# PIC18F97J94.net
KiCad netlist of a schematic drawn in Altium Designer
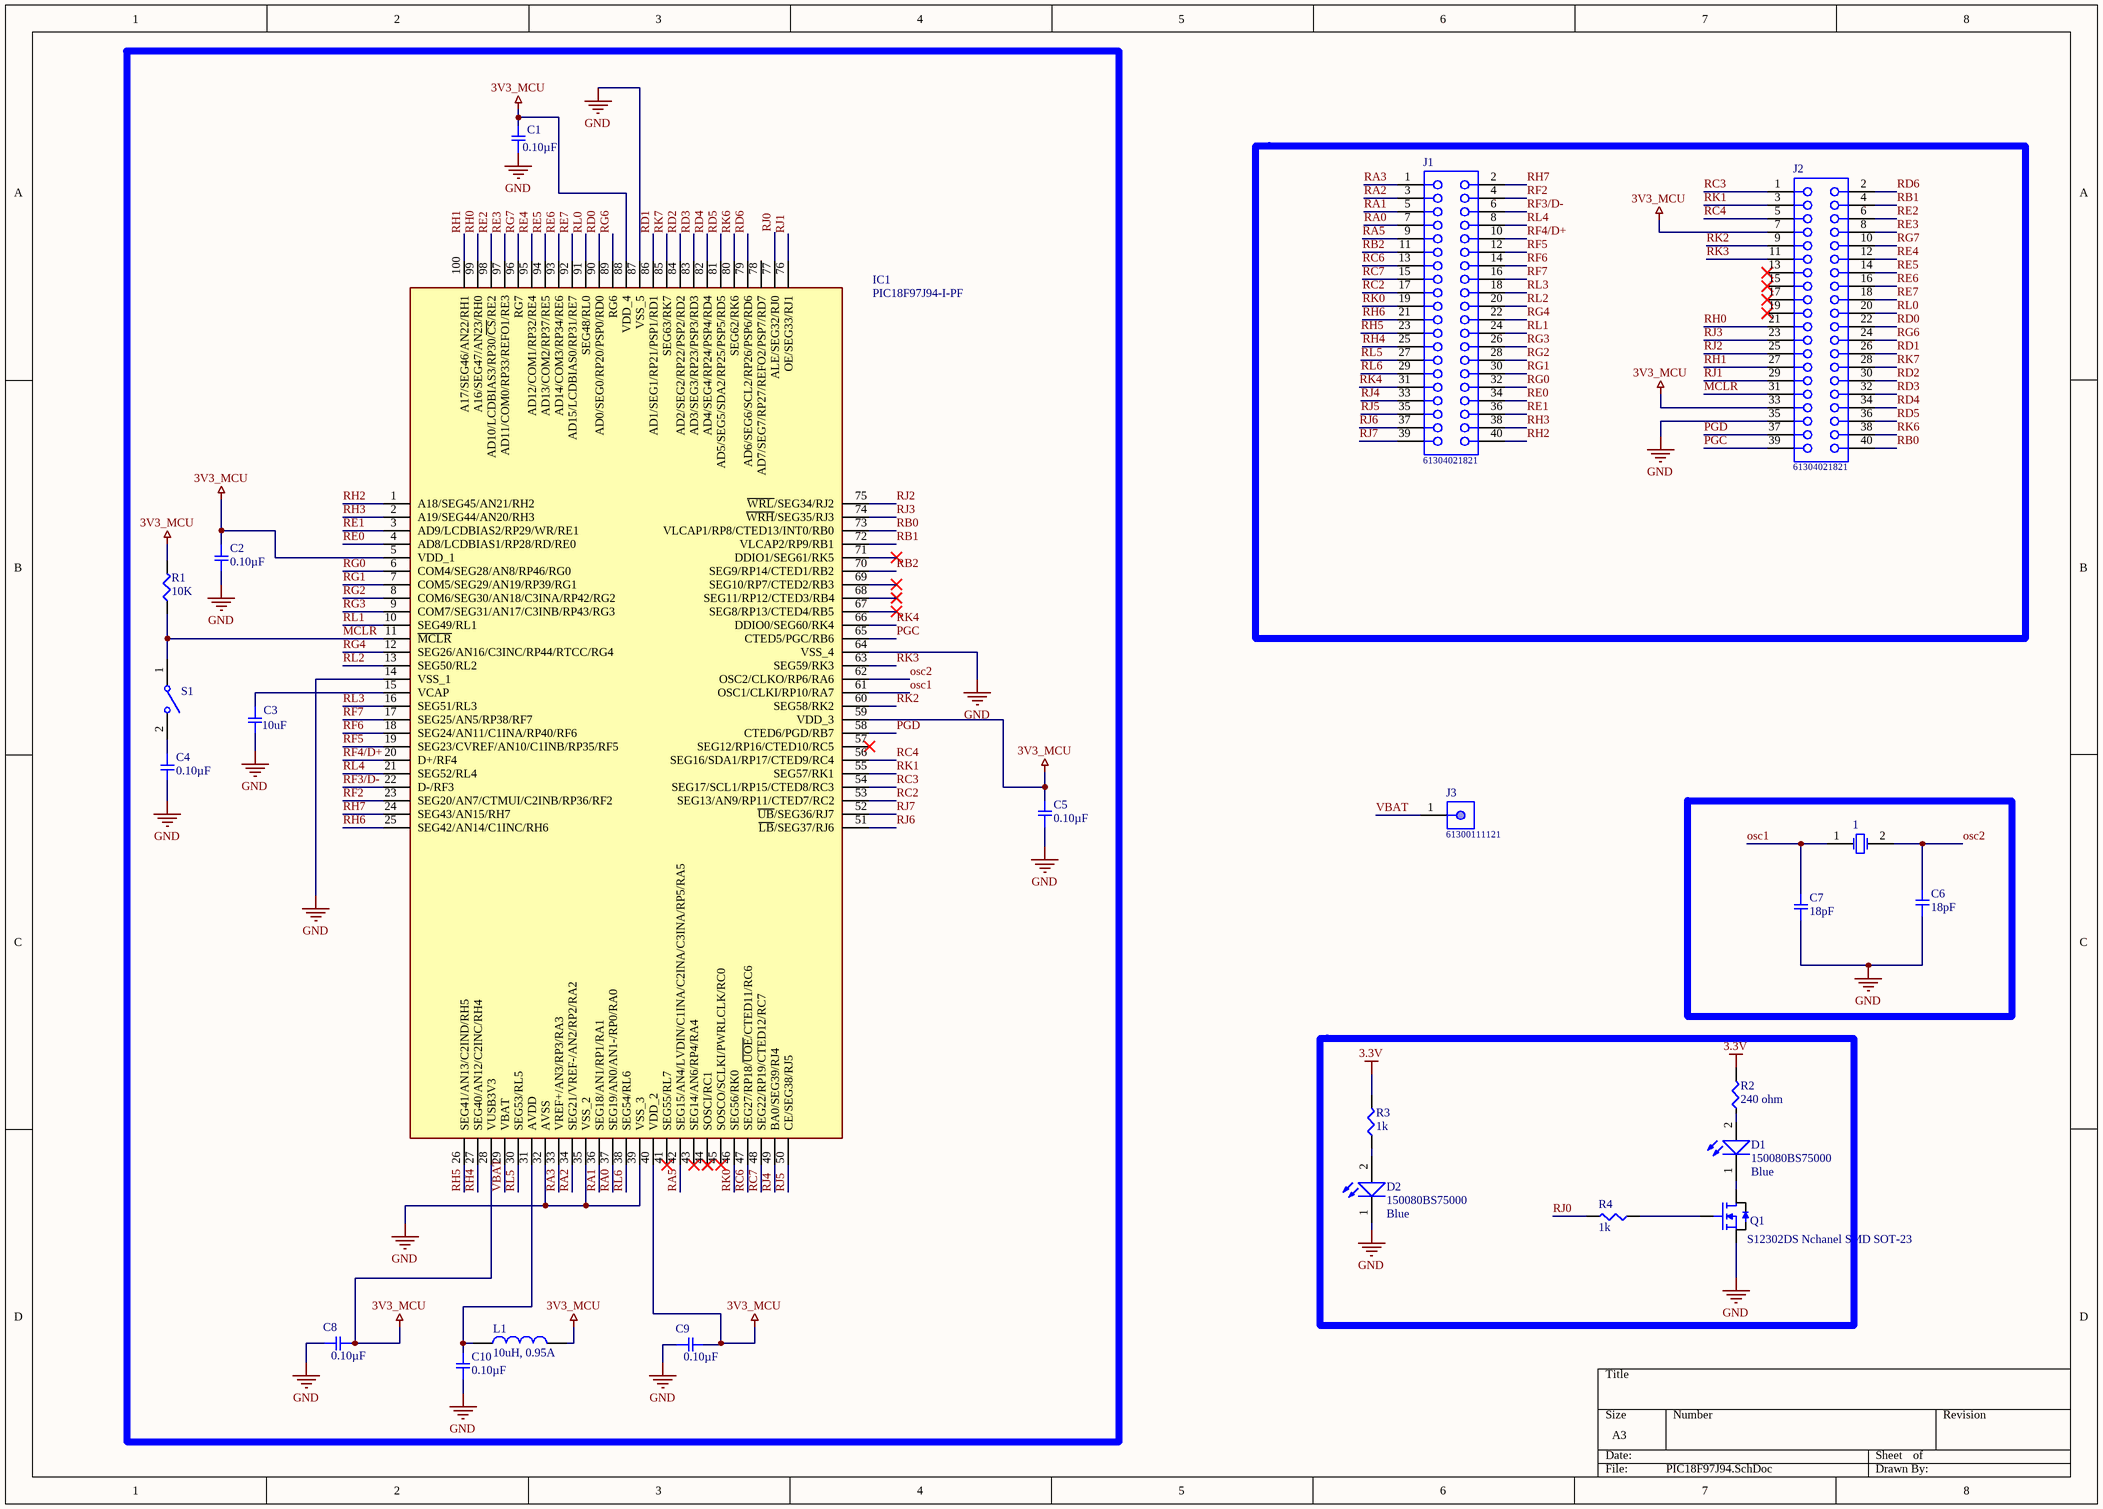
[diagram p0: PIC18F97J94.SchDoc]

(export (version "E")
  (design (tool "Eeschema 10.0.6"))
  (components
    (comp (ref "1")
      (value "~")
      (footprint "Mini Crystal")
      (description "9B-64.000MBBK-B")
      (fields (field (name "MANUFACTURER") "Abracon") (field (name "PARTNUMBER") "ABLS2-4.096MHZ-D4Y-T"))
      (libsource (lib "Medi Custom library") (part "Mini Crystal"))
    )
    (comp (ref "C1")
      (value "0.10µF")
      (footprint "SMD-0805C")
      (description "CAP CER 0.1UF 50V X7R 0805")
      (fields
        (field (name "DIGI-KEY PART NUMBER") "490-11955-1-ND")
        (field (name "PART NUMBER") "GCD21BR71H104KA01L")
      )
      (libsource (lib "capacitor_murata_0805") (part "GCD21BR71H104KA01L"))
    )
    (comp (ref "C2")
      (value "0.10µF")
      (footprint "SMD-0805C")
      (description "CAP CER 0.1UF 50V X7R 0805")
      (fields
        (field (name "DIGI-KEY PART NUMBER") "490-11955-1-ND")
        (field (name "PART NUMBER") "GCD21BR71H104KA01L")
      )
      (libsource (lib "capacitor_murata_0805") (part "GCD21BR71H104KA01L"))
    )
    (comp (ref "C3")
      (value "10uF")
      (footprint "SMD-0805C")
      (description "CAP CER 0.1UF 50V X7R 0805")
      (fields
        (field (name "DIGI-KEY PART NUMBER") "490-11955-1-ND")
        (field (name "PART NUMBER") "GCD21BR71H104KA01L")
      )
      (libsource (lib "capacitor_murata_0805") (part "GCD21BR71H104KA01L"))
    )
    (comp (ref "C4")
      (value "0.10µF")
      (footprint "SMD-0805C")
      (description "CAP CER 0.1UF 50V X7R 0805")
      (fields
        (field (name "DIGI-KEY PART NUMBER") "490-11955-1-ND")
        (field (name "PART NUMBER") "GCD21BR71H104KA01L")
      )
      (libsource (lib "capacitor_murata_0805") (part "GCD21BR71H104KA01L"))
    )
    (comp (ref "C5")
      (value "0.10µF")
      (footprint "SMD-0805C")
      (description "CAP CER 0.1UF 50V X7R 0805")
      (fields
        (field (name "DIGI-KEY PART NUMBER") "490-11955-1-ND")
        (field (name "PART NUMBER") "GCD21BR71H104KA01L")
      )
      (libsource (lib "capacitor_murata_0805") (part "GCD21BR71H104KA01L"))
    )
    (comp (ref "C6")
      (value "18pF")
      (footprint "SMD-0805C")
      (description "CAP CER 0.1UF 50V X7R 0805")
      (fields
        (field (name "DIGI-KEY PART NUMBER") "490-11955-1-ND")
        (field (name "PART NUMBER") "GCD21BR71H104KA01L")
      )
      (libsource (lib "capacitor_murata_0805") (part "GCD21BR71H104KA01L"))
    )
    (comp (ref "C7")
      (value "18pF")
      (footprint "SMD-0805C")
      (description "CAP CER 0.1UF 50V X7R 0805")
      (fields
        (field (name "DIGI-KEY PART NUMBER") "490-11955-1-ND")
        (field (name "PART NUMBER") "GCD21BR71H104KA01L")
      )
      (libsource (lib "capacitor_murata_0805") (part "GCD21BR71H104KA01L"))
    )
    (comp (ref "C8")
      (value "0.10µF")
      (footprint "SMD-0805C")
      (description "CAP CER 0.1UF 50V X7R 0805")
      (fields
        (field (name "DIGI-KEY PART NUMBER") "490-11955-1-ND")
        (field (name "PART NUMBER") "GCD21BR71H104KA01L")
      )
      (libsource (lib "capacitor_murata_0805") (part "GCD21BR71H104KA01L"))
    )
    (comp (ref "C9")
      (value "0.10µF")
      (footprint "SMD-0805C")
      (description "CAP CER 0.1UF 50V X7R 0805")
      (fields
        (field (name "DIGI-KEY PART NUMBER") "490-11955-1-ND")
        (field (name "PART NUMBER") "GCD21BR71H104KA01L")
      )
      (libsource (lib "capacitor_murata_0805") (part "GCD21BR71H104KA01L"))
    )
    (comp (ref "C10")
      (value "0.10µF")
      (footprint "SMD-0805C")
      (description "CAP CER 0.1UF 50V X7R 0805")
      (fields
        (field (name "DIGI-KEY PART NUMBER") "490-11955-1-ND")
        (field (name "PART NUMBER") "GCD21BR71H104KA01L")
      )
      (libsource (lib "capacitor_murata_0805") (part "GCD21BR71H104KA01L"))
    )
    (comp (ref "D1")
      (value "150080BS75000")
      (footprint "WL-SMCW_0805")
      (description "WL-SMCW SMD Mono-color Chip LED Waterclear, size 0805, Blue")
      (fields (field (name "EMITTING COLOR") "Blue") (field (name "PUBLISHER") "Wurth Elektronik"))
      (libsource (lib "SMD LED 0603 t0 1206 WL-SMCW-SMT-LED") (part "150080BS75000"))
    )
    (comp (ref "D2")
      (value "150080BS75000")
      (footprint "WL-SMCW_0805")
      (description "WL-SMCW SMD Mono-color Chip LED Waterclear, size 0805, Blue")
      (fields (field (name "EMITTING COLOR") "Blue") (field (name "PUBLISHER") "Wurth Elektronik"))
      (libsource (lib "SMD LED 0603 t0 1206 WL-SMCW-SMT-LED") (part "150080BS75000"))
    )
    (comp (ref "IC1")
      (value "PIC18F97J94-I-PF")
      (footprint "SamacSys:QFP50P1600X1600X120-100N")
      (description "Integrated Circuit")
      (fields (field (name "MOUSER PART NUMBER") "579-PIC18F97J94-I/PF"))
      (libsource (lib "*") (part "PIC18F97J94-I-PF"))
    )
    (comp (ref "J1")
      (value "61304021821")
      (footprint "61304021821")
      (description "WR-PHD Socket Header, THT, pitch 2.54mm, Dual Row, Vertical, 40pin")
      (fields (field (name "PUBLISHER") "Wurth Elektronik"))
      (libsource (lib "SIL_Connectors WR-PHD_rev19a") (part "61304021821"))
    )
    (comp (ref "J2")
      (value "61304021821")
      (footprint "61304021821")
      (description "WR-PHD Socket Header, THT, pitch 2.54mm, Dual Row, Vertical, 40pin")
      (fields (field (name "PUBLISHER") "Wurth Elektronik"))
      (libsource (lib "SIL_Connectors WR-PHD_rev19a") (part "61304021821"))
    )
    (comp (ref "J3")
      (value "61300111121")
      (footprint "61300111121")
      (description "WR-PHD Pin Header, THT, pitch 2.54mm, Single Row, Vertical, 1pin")
      (fields (field (name "PUBLISHER") "Wurth Elektronik"))
      (libsource (lib "SIL_Connectors WR-PHD_rev19a") (part "61300111121"))
    )
    (comp (ref "L1")
      (value "10uH, 0.95A")
      (footprint "WE-LQ_1812")
      (description "WE-LQ SMT Inductor, size 1812, 10uH, 0.95A")
      (fields
        (field (name "MANUFACTURER PART NUMBER") "744045100")
        (field (name "MANUFACTURER") "Wurth Elektronik")
      )
      (libsource (lib "SMD inductor 1WE-LQ_rev20a") (part "744045100"))
    )
    (comp (ref "Q1")
      (value "S12302DS Nchanel SMD SOT-23")
      (footprint "SOT-23-3N")
      (description "S12302DS Nchanel SMD SOT-23. VDS MAX 20. 400Ma DI")
      (libsource (lib "My mosfet and Transistors Library") (part "S12302DS"))
    )
    (comp (ref "R1")
      (value "10K")
      (footprint "SMD-0805-RES")
      (description "RES SMD 1K OHM 1% 1/8W 0805")
      (fields
        (field (name "PART NUMBER") "ERJ-6ENF1001V")
        (field (name "DIGI-KEY PART NUMBER") "P1.00KCCT-ND")
      )
      (libsource (lib "Panasonic_ERJ_0805") (part "ERJ-6ENF1001V"))
    )
    (comp (ref "R2")
      (value "240 ohm")
      (footprint "SMD-0805-RES")
      (description "RES SMD 1K OHM 1% 1/8W 0805")
      (fields
        (field (name "PART NUMBER") "ERJ-6ENF1001V")
        (field (name "DIGI-KEY PART NUMBER") "P1.00KCCT-ND")
      )
      (libsource (lib "Panasonic_ERJ_0805") (part "ERJ-6ENF1001V"))
    )
    (comp (ref "R3")
      (value "1k")
      (footprint "SMD-0805-RES")
      (description "RES SMD 1K OHM 1% 1/8W 0805")
      (fields
        (field (name "PART NUMBER") "ERJ-6ENF1001V")
        (field (name "DIGI-KEY PART NUMBER") "P1.00KCCT-ND")
      )
      (libsource (lib "Panasonic_ERJ_0805") (part "ERJ-6ENF1001V"))
    )
    (comp (ref "R4")
      (value "1k")
      (footprint "SMD-0805-RES")
      (description "RES SMD 1K OHM 1% 1/8W 0805")
      (fields
        (field (name "PART NUMBER") "ERJ-6ENF1001V")
        (field (name "DIGI-KEY PART NUMBER") "P1.00KCCT-ND")
      )
      (libsource (lib "Panasonic_ERJ_0805") (part "ERJ-6ENF1001V"))
    )
    (comp (ref "S1")
      (value "434113043826")
      (footprint "434113043826")
      (description "WS-TASV J-Bend SMT Tact Switch 6x3.5mm, height 4.3mm, 260gf")
      (fields (field (name "PUBLISHER") "Wurth Elektronik"))
      (libsource (lib "SMD tact switch") (part "434113043826"))
    )
  )
  (nets
    (net (code "1") (name "/MCLR") (class "Default")
      (node (ref "IC1") (pin "11") (pinfunction "~{MCLR}_11") (pintype "passive"))
      (node (ref "J2") (pin "31") (pinfunction "31_31") (pintype "passive"))
      (node (ref "R1") (pin "1") (pinfunction "1_1") (pintype "passive"))
      (node (ref "S1") (pin "1") (pinfunction "1_1") (pintype "passive"))
    )
    (net (code "2") (name "/PGC") (class "Default")
      (node (ref "IC1") (pin "65") (pinfunction "CTED5/PGC/RB6_65") (pintype "passive"))
      (node (ref "J2") (pin "39") (pinfunction "39_39") (pintype "passive"))
    )
    (net (code "3") (name "/PGD") (class "Default")
      (node (ref "IC1") (pin "58") (pinfunction "CTED6/PGD/RB7_58") (pintype "passive"))
      (node (ref "J2") (pin "37") (pinfunction "37_37") (pintype "passive"))
    )
    (net (code "4") (name "/RA0") (class "Default")
      (node (ref "IC1") (pin "37") (pinfunction "SEG19/AN0/AN1-/RP0/RA0_37") (pintype "passive"))
      (node (ref "J1") (pin "7") (pinfunction "7_7") (pintype "passive"))
    )
    (net (code "5") (name "/RA1") (class "Default")
      (node (ref "IC1") (pin "36") (pinfunction "SEG18/AN1/RP1/RA1_36") (pintype "passive"))
      (node (ref "J1") (pin "5") (pinfunction "5_5") (pintype "passive"))
    )
    (net (code "6") (name "/RA2") (class "Default")
      (node (ref "IC1") (pin "34") (pinfunction "SEG21/VREF-/AN2/RP2/RA2_34") (pintype "passive"))
      (node (ref "J1") (pin "3") (pinfunction "3_3") (pintype "passive"))
    )
    (net (code "7") (name "/RA3") (class "Default")
      (node (ref "IC1") (pin "33") (pinfunction "VREF+/AN3/RP3/RA3_33") (pintype "passive"))
      (node (ref "J1") (pin "1") (pinfunction "1_1") (pintype "passive"))
    )
    (net (code "8") (name "/RA5") (class "Default")
      (node (ref "IC1") (pin "42") (pinfunction "SEG15/AN4/LVDIN/C1INA/C2INA/C3INA/RP5/RA5_42") (pintype "passive"))
      (node (ref "J1") (pin "9") (pinfunction "9_9") (pintype "passive"))
    )
    (net (code "9") (name "/RB0") (class "Default")
      (node (ref "IC1") (pin "73") (pinfunction "VLCAP1/RP8/CTED13/INT0/RB0_73") (pintype "passive"))
      (node (ref "J2") (pin "40") (pinfunction "40_40") (pintype "passive"))
    )
    (net (code "10") (name "/RB1") (class "Default")
      (node (ref "IC1") (pin "72") (pinfunction "VLCAP2/RP9/RB1_72") (pintype "passive"))
      (node (ref "J2") (pin "4") (pinfunction "4_4") (pintype "passive"))
    )
    (net (code "11") (name "/RB2") (class "Default")
      (node (ref "IC1") (pin "70") (pinfunction "SEG9/RP14/CTED1/RB2_70") (pintype "passive"))
      (node (ref "J1") (pin "11") (pinfunction "11_11") (pintype "passive"))
    )
    (net (code "12") (name "/RC2") (class "Default")
      (node (ref "IC1") (pin "53") (pinfunction "SEG13/AN9/RP11/CTED7/RC2_53") (pintype "passive"))
      (node (ref "J1") (pin "17") (pinfunction "17_17") (pintype "passive"))
    )
    (net (code "13") (name "/RC3") (class "Default")
      (node (ref "IC1") (pin "54") (pinfunction "SEG17/SCL1/RP15/CTED8/RC3_54") (pintype "passive"))
      (node (ref "J2") (pin "1") (pinfunction "1_1") (pintype "passive"))
    )
    (net (code "14") (name "/RC4") (class "Default")
      (node (ref "IC1") (pin "56") (pinfunction "SEG16/SDA1/RP17/CTED9/RC4_56") (pintype "passive"))
      (node (ref "J2") (pin "5") (pinfunction "5_5") (pintype "passive"))
    )
    (net (code "15") (name "/RC6") (class "Default")
      (node (ref "IC1") (pin "47") (pinfunction "SEG27/RP18/~{UOE}/CTED11/RC6_47") (pintype "passive"))
      (node (ref "J1") (pin "13") (pinfunction "13_13") (pintype "passive"))
    )
    (net (code "16") (name "/RC7") (class "Default")
      (node (ref "IC1") (pin "48") (pinfunction "SEG22/RP19/CTED12/RC7_48") (pintype "passive"))
      (node (ref "J1") (pin "15") (pinfunction "15_15") (pintype "passive"))
    )
    (net (code "17") (name "/RD0") (class "Default")
      (node (ref "IC1") (pin "90") (pinfunction "AD0/SEG0/RP20/PSP0/RD0_90") (pintype "passive"))
      (node (ref "J2") (pin "22") (pinfunction "22_22") (pintype "passive"))
    )
    (net (code "18") (name "/RD1") (class "Default")
      (node (ref "IC1") (pin "86") (pinfunction "AD1/SEG1/RP21/PSP1/RD1_86") (pintype "passive"))
      (node (ref "J2") (pin "26") (pinfunction "26_26") (pintype "passive"))
    )
    (net (code "19") (name "/RD2") (class "Default")
      (node (ref "IC1") (pin "84") (pinfunction "AD2/SEG2/RP22/PSP2/RD2_84") (pintype "passive"))
      (node (ref "J2") (pin "30") (pinfunction "30_30") (pintype "passive"))
    )
    (net (code "20") (name "/RD3") (class "Default")
      (node (ref "IC1") (pin "83") (pinfunction "AD3/SEG3/RP23/PSP3/RD3_83") (pintype "passive"))
      (node (ref "J2") (pin "32") (pinfunction "32_32") (pintype "passive"))
    )
    (net (code "21") (name "/RD4") (class "Default")
      (node (ref "IC1") (pin "82") (pinfunction "AD4/SEG4/RP24/PSP4/RD4_82") (pintype "passive"))
      (node (ref "J2") (pin "34") (pinfunction "34_34") (pintype "passive"))
    )
    (net (code "22") (name "/RD5") (class "Default")
      (node (ref "IC1") (pin "81") (pinfunction "AD5/SEG5/SDA2/RP25/PSP5/RD5_81") (pintype "passive"))
      (node (ref "J2") (pin "36") (pinfunction "36_36") (pintype "passive"))
    )
    (net (code "23") (name "/RD6") (class "Default")
      (node (ref "IC1") (pin "79") (pinfunction "AD6/SEG6/SCL2/RP26/PSP6/RD6_79") (pintype "passive"))
      (node (ref "J2") (pin "2") (pinfunction "2_2") (pintype "passive"))
    )
    (net (code "24") (name "/RE0") (class "Default")
      (node (ref "IC1") (pin "4") (pinfunction "AD8/LCDBIAS1/RP28/RD/RE0_4") (pintype "passive"))
      (node (ref "J1") (pin "34") (pinfunction "34_34") (pintype "passive"))
    )
    (net (code "25") (name "/RE1") (class "Default")
      (node (ref "IC1") (pin "3") (pinfunction "AD9/LCDBIAS2/RP29/WR/RE1_3") (pintype "passive"))
      (node (ref "J1") (pin "36") (pinfunction "36_36") (pintype "passive"))
    )
    (net (code "26") (name "/RE2") (class "Default")
      (node (ref "IC1") (pin "98") (pinfunction "AD10/LCDBIAS3/RP30/~{CS}/RE2_98") (pintype "passive"))
      (node (ref "J2") (pin "6") (pinfunction "6_6") (pintype "passive"))
    )
    (net (code "27") (name "/RE3") (class "Default")
      (node (ref "IC1") (pin "97") (pinfunction "AD11/COM0/RP33/REFO1/RE3_97") (pintype "passive"))
      (node (ref "J2") (pin "8") (pinfunction "8_8") (pintype "passive"))
    )
    (net (code "28") (name "/RE4") (class "Default")
      (node (ref "IC1") (pin "95") (pinfunction "AD12/COM1/RP32/RE4_95") (pintype "passive"))
      (node (ref "J2") (pin "12") (pinfunction "12_12") (pintype "passive"))
    )
    (net (code "29") (name "/RE5") (class "Default")
      (node (ref "IC1") (pin "94") (pinfunction "AD13/COM2/RP37/RE5_94") (pintype "passive"))
      (node (ref "J2") (pin "14") (pinfunction "14_14") (pintype "passive"))
    )
    (net (code "30") (name "/RE6") (class "Default")
      (node (ref "IC1") (pin "93") (pinfunction "AD14/COM3/RP34/RE6_93") (pintype "passive"))
      (node (ref "J2") (pin "16") (pinfunction "16_16") (pintype "passive"))
    )
    (net (code "31") (name "/RE7") (class "Default")
      (node (ref "IC1") (pin "92") (pinfunction "AD15/LCDBIAS0/RP31/RE7_92") (pintype "passive"))
      (node (ref "J2") (pin "18") (pinfunction "18_18") (pintype "passive"))
    )
    (net (code "32") (name "/RF2") (class "Default")
      (node (ref "IC1") (pin "23") (pinfunction "SEG20/AN7/CTMUI/C2INB/RP36/RF2_23") (pintype "passive"))
      (node (ref "J1") (pin "4") (pinfunction "4_4") (pintype "passive"))
    )
    (net (code "33") (name "/RF3{slash}D-") (class "Default")
      (node (ref "IC1") (pin "22") (pinfunction "D-/RF3_22") (pintype "passive"))
      (node (ref "J1") (pin "6") (pinfunction "6_6") (pintype "passive"))
    )
    (net (code "34") (name "/RF4{slash}D+") (class "Default")
      (node (ref "IC1") (pin "20") (pinfunction "D+/RF4_20") (pintype "passive"))
      (node (ref "J1") (pin "10") (pinfunction "10_10") (pintype "passive"))
    )
    (net (code "35") (name "/RF5") (class "Default")
      (node (ref "IC1") (pin "19") (pinfunction "SEG23/CVREF/AN10/C1INB/RP35/RF5_19") (pintype "passive"))
      (node (ref "J1") (pin "12") (pinfunction "12_12") (pintype "passive"))
    )
    (net (code "36") (name "/RF6") (class "Default")
      (node (ref "IC1") (pin "18") (pinfunction "SEG24/AN11/C1INA/RP40/RF6_18") (pintype "passive"))
      (node (ref "J1") (pin "14") (pinfunction "14_14") (pintype "passive"))
    )
    (net (code "37") (name "/RF7") (class "Default")
      (node (ref "IC1") (pin "17") (pinfunction "SEG25/AN5/RP38/RF7_17") (pintype "passive"))
      (node (ref "J1") (pin "16") (pinfunction "16_16") (pintype "passive"))
    )
    (net (code "38") (name "/RG0") (class "Default")
      (node (ref "IC1") (pin "6") (pinfunction "COM4/SEG28/AN8/RP46/RG0_6") (pintype "passive"))
      (node (ref "J1") (pin "32") (pinfunction "32_32") (pintype "passive"))
    )
    (net (code "39") (name "/RG1") (class "Default")
      (node (ref "IC1") (pin "7") (pinfunction "COM5/SEG29/AN19/RP39/RG1_7") (pintype "passive"))
      (node (ref "J1") (pin "30") (pinfunction "30_30") (pintype "passive"))
    )
    (net (code "40") (name "/RG2") (class "Default")
      (node (ref "IC1") (pin "8") (pinfunction "COM6/SEG30/AN18/C3INA/RP42/RG2_8") (pintype "passive"))
      (node (ref "J1") (pin "28") (pinfunction "28_28") (pintype "passive"))
    )
    (net (code "41") (name "/RG3") (class "Default")
      (node (ref "IC1") (pin "9") (pinfunction "COM7/SEG31/AN17/C3INB/RP43/RG3_9") (pintype "passive"))
      (node (ref "J1") (pin "26") (pinfunction "26_26") (pintype "passive"))
    )
    (net (code "42") (name "/RG4") (class "Default")
      (node (ref "IC1") (pin "12") (pinfunction "SEG26/AN16/C3INC/RP44/RTCC/RG4_12") (pintype "passive"))
      (node (ref "J1") (pin "22") (pinfunction "22_22") (pintype "passive"))
    )
    (net (code "43") (name "/RG6") (class "Default")
      (node (ref "IC1") (pin "89") (pinfunction "RG6_89") (pintype "passive"))
      (node (ref "J2") (pin "24") (pinfunction "24_24") (pintype "passive"))
    )
    (net (code "44") (name "/RG7") (class "Default")
      (node (ref "IC1") (pin "96") (pinfunction "RG7_96") (pintype "passive"))
      (node (ref "J2") (pin "10") (pinfunction "10_10") (pintype "passive"))
    )
    (net (code "45") (name "/RH0") (class "Default")
      (node (ref "IC1") (pin "99") (pinfunction "A16/SEG47/AN23/RH0_99") (pintype "passive"))
      (node (ref "J2") (pin "21") (pinfunction "21_21") (pintype "passive"))
    )
    (net (code "46") (name "/RH1") (class "Default")
      (node (ref "IC1") (pin "100") (pinfunction "A17/SEG46/AN22/RH1_100") (pintype "passive"))
      (node (ref "J2") (pin "27") (pinfunction "27_27") (pintype "passive"))
    )
    (net (code "47") (name "/RH2") (class "Default")
      (node (ref "IC1") (pin "1") (pinfunction "A18/SEG45/AN21/RH2_1") (pintype "passive"))
      (node (ref "J1") (pin "40") (pinfunction "40_40") (pintype "passive"))
    )
    (net (code "48") (name "/RH3") (class "Default")
      (node (ref "IC1") (pin "2") (pinfunction "A19/SEG44/AN20/RH3_2") (pintype "passive"))
      (node (ref "J1") (pin "38") (pinfunction "38_38") (pintype "passive"))
    )
    (net (code "49") (name "/RH4") (class "Default")
      (node (ref "IC1") (pin "27") (pinfunction "SEG40/AN12/C2INC/RH4_27") (pintype "passive"))
      (node (ref "J1") (pin "25") (pinfunction "25_25") (pintype "passive"))
    )
    (net (code "50") (name "/RH5") (class "Default")
      (node (ref "IC1") (pin "26") (pinfunction "SEG41/AN13/C2IND/RH5_26") (pintype "passive"))
      (node (ref "J1") (pin "23") (pinfunction "23_23") (pintype "passive"))
    )
    (net (code "51") (name "/RH6") (class "Default")
      (node (ref "IC1") (pin "25") (pinfunction "SEG42/AN14/C1INC/RH6_25") (pintype "passive"))
      (node (ref "J1") (pin "21") (pinfunction "21_21") (pintype "passive"))
    )
    (net (code "52") (name "/RH7") (class "Default")
      (node (ref "IC1") (pin "24") (pinfunction "SEG43/AN15/RH7_24") (pintype "passive"))
      (node (ref "J1") (pin "2") (pinfunction "2_2") (pintype "passive"))
    )
    (net (code "53") (name "/RJ0") (class "Default")
      (node (ref "IC1") (pin "77") (pinfunction "ALE/SEG32/RJ0_77") (pintype "passive"))
      (node (ref "R4") (pin "2") (pinfunction "2_2") (pintype "passive"))
    )
    (net (code "54") (name "/RJ1") (class "Default")
      (node (ref "IC1") (pin "76") (pinfunction "OE/SEG33/RJ1_76") (pintype "passive"))
      (node (ref "J2") (pin "29") (pinfunction "29_29") (pintype "passive"))
    )
    (net (code "55") (name "/RJ2") (class "Default")
      (node (ref "IC1") (pin "75") (pinfunction "~{WRL}/SEG34/RJ2_75") (pintype "passive"))
      (node (ref "J2") (pin "25") (pinfunction "25_25") (pintype "passive"))
    )
    (net (code "56") (name "/RJ3") (class "Default")
      (node (ref "IC1") (pin "74") (pinfunction "~{WRH}/SEG35/RJ3_74") (pintype "passive"))
      (node (ref "J2") (pin "23") (pinfunction "23_23") (pintype "passive"))
    )
    (net (code "57") (name "/RJ4") (class "Default")
      (node (ref "IC1") (pin "49") (pinfunction "BA0/SEG39/RJ4_49") (pintype "passive"))
      (node (ref "J1") (pin "33") (pinfunction "33_33") (pintype "passive"))
    )
    (net (code "58") (name "/RJ5") (class "Default")
      (node (ref "IC1") (pin "50") (pinfunction "CE/SEG38/RJ5_50") (pintype "passive"))
      (node (ref "J1") (pin "35") (pinfunction "35_35") (pintype "passive"))
    )
    (net (code "59") (name "/RJ6") (class "Default")
      (node (ref "IC1") (pin "51") (pinfunction "~{LB}/SEG37/RJ6_51") (pintype "passive"))
      (node (ref "J1") (pin "37") (pinfunction "37_37") (pintype "passive"))
    )
    (net (code "60") (name "/RJ7") (class "Default")
      (node (ref "IC1") (pin "52") (pinfunction "~{UB}/SEG36/RJ7_52") (pintype "passive"))
      (node (ref "J1") (pin "39") (pinfunction "39_39") (pintype "passive"))
    )
    (net (code "61") (name "/RK0") (class "Default")
      (node (ref "IC1") (pin "46") (pinfunction "SEG56/RK0_46") (pintype "passive"))
      (node (ref "J1") (pin "19") (pinfunction "19_19") (pintype "passive"))
    )
    (net (code "62") (name "/RK1") (class "Default")
      (node (ref "IC1") (pin "55") (pinfunction "SEG57/RK1_55") (pintype "passive"))
      (node (ref "J2") (pin "3") (pinfunction "3_3") (pintype "passive"))
    )
    (net (code "63") (name "/RK2") (class "Default")
      (node (ref "IC1") (pin "60") (pinfunction "SEG58/RK2_60") (pintype "passive"))
      (node (ref "J2") (pin "9") (pinfunction "9_9") (pintype "passive"))
    )
    (net (code "64") (name "/RK3") (class "Default")
      (node (ref "IC1") (pin "63") (pinfunction "SEG59/RK3_63") (pintype "passive"))
      (node (ref "J2") (pin "11") (pinfunction "11_11") (pintype "passive"))
    )
    (net (code "65") (name "/RK4") (class "Default")
      (node (ref "IC1") (pin "66") (pinfunction "DDIO0/SEG60/RK4_66") (pintype "passive"))
      (node (ref "J1") (pin "31") (pinfunction "31_31") (pintype "passive"))
    )
    (net (code "66") (name "/RK6") (class "Default")
      (node (ref "IC1") (pin "80") (pinfunction "SEG62/RK6_80") (pintype "passive"))
      (node (ref "J2") (pin "38") (pinfunction "38_38") (pintype "passive"))
    )
    (net (code "67") (name "/RK7") (class "Default")
      (node (ref "IC1") (pin "85") (pinfunction "SEG63/RK7_85") (pintype "passive"))
      (node (ref "J2") (pin "28") (pinfunction "28_28") (pintype "passive"))
    )
    (net (code "68") (name "/RL0") (class "Default")
      (node (ref "IC1") (pin "91") (pinfunction "SEG48/RL0_91") (pintype "passive"))
      (node (ref "J2") (pin "20") (pinfunction "20_20") (pintype "passive"))
    )
    (net (code "69") (name "/RL1") (class "Default")
      (node (ref "IC1") (pin "10") (pinfunction "SEG49/RL1_10") (pintype "passive"))
      (node (ref "J1") (pin "24") (pinfunction "24_24") (pintype "passive"))
    )
    (net (code "70") (name "/RL2") (class "Default")
      (node (ref "IC1") (pin "13") (pinfunction "SEG50/RL2_13") (pintype "passive"))
      (node (ref "J1") (pin "20") (pinfunction "20_20") (pintype "passive"))
    )
    (net (code "71") (name "/RL3") (class "Default")
      (node (ref "IC1") (pin "16") (pinfunction "SEG51/RL3_16") (pintype "passive"))
      (node (ref "J1") (pin "18") (pinfunction "18_18") (pintype "passive"))
    )
    (net (code "72") (name "/RL4") (class "Default")
      (node (ref "IC1") (pin "21") (pinfunction "SEG52/RL4_21") (pintype "passive"))
      (node (ref "J1") (pin "8") (pinfunction "8_8") (pintype "passive"))
    )
    (net (code "73") (name "/RL5") (class "Default")
      (node (ref "IC1") (pin "30") (pinfunction "SEG53/RL5_30") (pintype "passive"))
      (node (ref "J1") (pin "27") (pinfunction "27_27") (pintype "passive"))
    )
    (net (code "74") (name "/RL6") (class "Default")
      (node (ref "IC1") (pin "38") (pinfunction "SEG54/RL6_38") (pintype "passive"))
      (node (ref "J1") (pin "29") (pinfunction "29_29") (pintype "passive"))
    )
    (net (code "75") (name "/VBAT") (class "Default")
      (node (ref "IC1") (pin "29") (pinfunction "VBAT_29") (pintype "passive"))
      (node (ref "J3") (pin "1") (pinfunction "1_1") (pintype "passive"))
    )
    (net (code "76") (name "/osc1") (class "Default")
      (node (ref "1") (pin "1") (pinfunction "X1_1") (pintype "passive"))
      (node (ref "C7") (pin "2") (pinfunction "2_2") (pintype "passive"))
      (node (ref "IC1") (pin "61") (pinfunction "OSC1/CLKI/RP10/RA7_61") (pintype "passive"))
    )
    (net (code "77") (name "/osc2") (class "Default")
      (node (ref "1") (pin "2") (pinfunction "X2_2") (pintype "passive"))
      (node (ref "C6") (pin "2") (pinfunction "2_2") (pintype "passive"))
      (node (ref "IC1") (pin "62") (pinfunction "OSC2/CLKO/RP6/RA6_62") (pintype "passive"))
    )
    (net (code "78") (name "3.3V") (class "Default")
      (node (ref "R2") (pin "2") (pinfunction "2_2") (pintype "passive"))
      (node (ref "R3") (pin "2") (pinfunction "2_2") (pintype "passive"))
    )
    (net (code "79") (name "3V3_MCU") (class "Default")
      (node (ref "C1") (pin "2") (pinfunction "2_2") (pintype "passive"))
      (node (ref "C2") (pin "1") (pinfunction "1_1") (pintype "passive"))
      (node (ref "C5") (pin "2") (pinfunction "2_2") (pintype "passive"))
      (node (ref "C8") (pin "2") (pinfunction "2_2") (pintype "passive"))
      (node (ref "C9") (pin "2") (pinfunction "2_2") (pintype "passive"))
      (node (ref "IC1") (pin "28") (pinfunction "VUSB3V3_28") (pintype "passive"))
      (node (ref "IC1") (pin "40") (pinfunction "VDD_2_40") (pintype "passive"))
      (node (ref "IC1") (pin "5") (pinfunction "VDD_1_5") (pintype "passive"))
      (node (ref "IC1") (pin "59") (pinfunction "VDD_3_59") (pintype "passive"))
      (node (ref "IC1") (pin "88") (pinfunction "VDD_4_88") (pintype "passive"))
      (node (ref "J2") (pin "33") (pinfunction "33_33") (pintype "passive"))
      (node (ref "J2") (pin "7") (pinfunction "7_7") (pintype "passive"))
      (node (ref "L1") (pin "2") (pinfunction "2_2") (pintype "passive"))
      (node (ref "R1") (pin "2") (pinfunction "2_2") (pintype "passive"))
    )
    (net (code "80") (name "GND") (class "Default")
      (node (ref "C1") (pin "1") (pinfunction "1_1") (pintype "passive"))
      (node (ref "C10") (pin "1") (pinfunction "1_1") (pintype "passive"))
      (node (ref "C2") (pin "2") (pinfunction "2_2") (pintype "passive"))
      (node (ref "C3") (pin "2") (pinfunction "2_2") (pintype "passive"))
      (node (ref "C4") (pin "2") (pinfunction "2_2") (pintype "passive"))
      (node (ref "C5") (pin "1") (pinfunction "1_1") (pintype "passive"))
      (node (ref "C6") (pin "1") (pinfunction "1_1") (pintype "passive"))
      (node (ref "C7") (pin "1") (pinfunction "1_1") (pintype "passive"))
      (node (ref "C8") (pin "1") (pinfunction "1_1") (pintype "passive"))
      (node (ref "C9") (pin "1") (pinfunction "1_1") (pintype "passive"))
      (node (ref "D2") (pin "1") (pinfunction "K_1") (pintype "passive"))
      (node (ref "IC1") (pin "14") (pinfunction "VSS_1_14") (pintype "passive"))
      (node (ref "IC1") (pin "32") (pinfunction "AVSS_32") (pintype "passive"))
      (node (ref "IC1") (pin "35") (pinfunction "VSS_2_35") (pintype "passive"))
      (node (ref "IC1") (pin "39") (pinfunction "VSS_3_39") (pintype "passive"))
      (node (ref "IC1") (pin "64") (pinfunction "VSS_4_64") (pintype "passive"))
      (node (ref "IC1") (pin "87") (pinfunction "VSS_5_87") (pintype "passive"))
      (node (ref "J2") (pin "35") (pinfunction "35_35") (pintype "passive"))
      (node (ref "Q1") (pin "2") (pinfunction "Source_2") (pintype "passive"))
    )
    (net (code "81") (name "Net-(C4-Pad1)") (class "Default")
      (node (ref "C4") (pin "1") (pinfunction "1_1") (pintype "passive"))
      (node (ref "S1") (pin "2") (pinfunction "2_2") (pintype "passive"))
    )
    (net (code "82") (name "Net-(D1-A)") (class "Default")
      (node (ref "D1") (pin "2") (pinfunction "A_2") (pintype "passive"))
      (node (ref "R2") (pin "1") (pinfunction "1_1") (pintype "passive"))
    )
    (net (code "83") (name "Net-(D1-K)") (class "Default")
      (node (ref "D1") (pin "1") (pinfunction "K_1") (pintype "passive"))
      (node (ref "Q1") (pin "3") (pinfunction "Drain_3") (pintype "passive"))
    )
    (net (code "84") (name "Net-(D2-A)") (class "Default")
      (node (ref "D2") (pin "2") (pinfunction "A_2") (pintype "passive"))
      (node (ref "R3") (pin "1") (pinfunction "1_1") (pintype "passive"))
    )
    (net (code "85") (name "Net-(IC1-AVDD)") (class "Default")
      (node (ref "C10") (pin "2") (pinfunction "2_2") (pintype "passive"))
      (node (ref "IC1") (pin "31") (pinfunction "AVDD_31") (pintype "passive"))
      (node (ref "L1") (pin "1") (pinfunction "1_1") (pintype "passive"))
    )
    (net (code "86") (name "Net-(IC1-VCAP)") (class "Default")
      (node (ref "C3") (pin "1") (pinfunction "1_1") (pintype "passive"))
      (node (ref "IC1") (pin "15") (pinfunction "VCAP_15") (pintype "passive"))
    )
    (net (code "87") (name "Net-(Q1-Gate)") (class "Default")
      (node (ref "Q1") (pin "1") (pinfunction "Gate_1") (pintype "passive"))
      (node (ref "R4") (pin "1") (pinfunction "1_1") (pintype "passive"))
    )
    (net (code "88") (name "unconnected-(IC1-AD7{slash}SEG7{slash}RP27{slash}REFO2{slash}PSP7{slash}RD7-Pad78)") (class "Default")
      (node (ref "IC1") (pin "78") (pinfunction "AD7/SEG7/RP27/REFO2/PSP7/RD7_78") (pintype "passive"))
    )
    (net (code "89") (name "unconnected-(IC1-DDIO1{slash}SEG61{slash}RK5-Pad71)") (class "Default")
      (node (ref "IC1") (pin "71") (pinfunction "DDIO1/SEG61/RK5_71") (pintype "passive+no_connect"))
    )
    (net (code "90") (name "unconnected-(IC1-SEG8{slash}RP13{slash}CTED4{slash}RB5-Pad67)") (class "Default")
      (node (ref "IC1") (pin "67") (pinfunction "SEG8/RP13/CTED4/RB5_67") (pintype "passive+no_connect"))
    )
    (net (code "91") (name "unconnected-(IC1-SEG10{slash}RP7{slash}CTED2{slash}RB3-Pad69)") (class "Default")
      (node (ref "IC1") (pin "69") (pinfunction "SEG10/RP7/CTED2/RB3_69") (pintype "passive+no_connect"))
    )
    (net (code "92") (name "unconnected-(IC1-SEG11{slash}RP12{slash}CTED3{slash}RB4-Pad68)") (class "Default")
      (node (ref "IC1") (pin "68") (pinfunction "SEG11/RP12/CTED3/RB4_68") (pintype "passive+no_connect"))
    )
    (net (code "93") (name "unconnected-(IC1-SEG12{slash}RP16{slash}CTED10{slash}RC5-Pad57)") (class "Default")
      (node (ref "IC1") (pin "57") (pinfunction "SEG12/RP16/CTED10/RC5_57") (pintype "passive+no_connect"))
    )
    (net (code "94") (name "unconnected-(IC1-SEG14{slash}AN6{slash}RP4{slash}RA4-Pad43)") (class "Default")
      (node (ref "IC1") (pin "43") (pinfunction "SEG14/AN6/RP4/RA4_43") (pintype "passive+no_connect"))
    )
    (net (code "95") (name "unconnected-(IC1-SEG55{slash}RL7-Pad41)") (class "Default")
      (node (ref "IC1") (pin "41") (pinfunction "SEG55/RL7_41") (pintype "passive+no_connect"))
    )
    (net (code "96") (name "unconnected-(IC1-SOSCI{slash}RC1-Pad44)") (class "Default")
      (node (ref "IC1") (pin "44") (pinfunction "SOSCI/RC1_44") (pintype "passive+no_connect"))
    )
    (net (code "97") (name "unconnected-(IC1-SOSCO{slash}SCLKI{slash}PWRLCLK{slash}RC0-Pad45)") (class "Default")
      (node (ref "IC1") (pin "45") (pinfunction "SOSCO/SCLKI/PWRLCLK/RC0_45") (pintype "passive+no_connect"))
    )
    (net (code "98") (name "unconnected-(J2-Pad13)") (class "Default")
      (node (ref "J2") (pin "13") (pinfunction "13_13") (pintype "passive+no_connect"))
    )
    (net (code "99") (name "unconnected-(J2-Pad15)") (class "Default")
      (node (ref "J2") (pin "15") (pinfunction "15_15") (pintype "passive+no_connect"))
    )
    (net (code "100") (name "unconnected-(J2-Pad17)") (class "Default")
      (node (ref "J2") (pin "17") (pinfunction "17_17") (pintype "passive+no_connect"))
    )
    (net (code "101") (name "unconnected-(J2-Pad19)") (class "Default")
      (node (ref "J2") (pin "19") (pinfunction "19_19") (pintype "passive+no_connect"))
    )
  )
)
